# pqm_v2_page4.net
KiCad netlist of a schematic drawn in Altium Designer
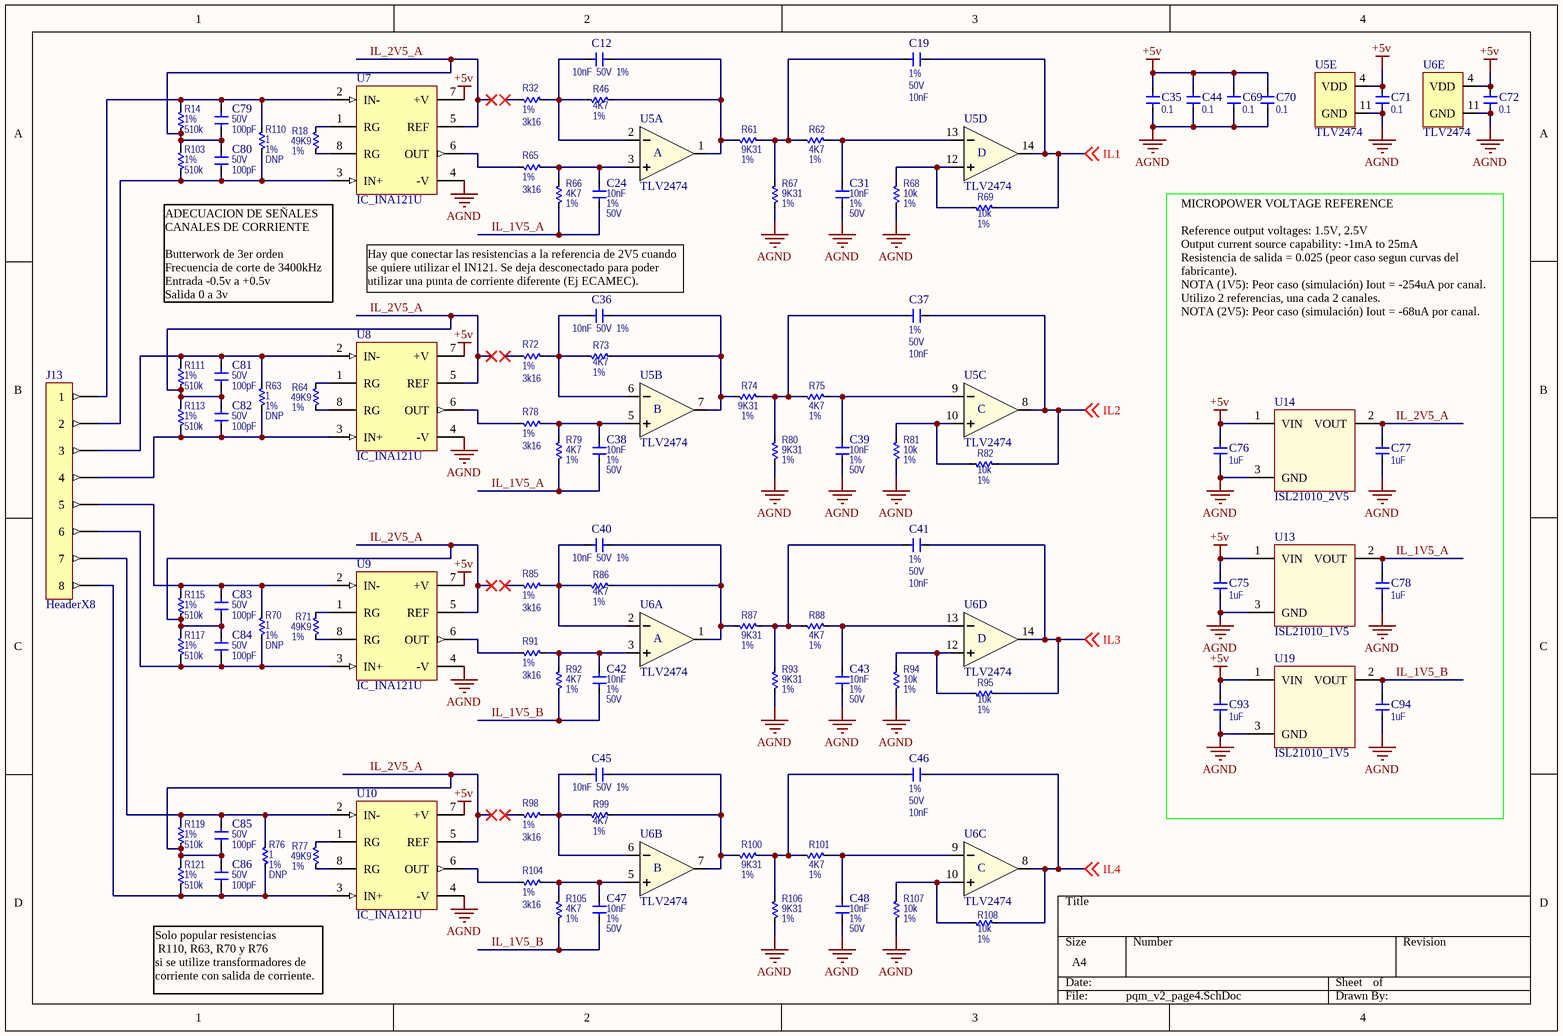
[diagram p0: pqm_v2_page4.SchDoc]

(export (version "E")
  (design (tool "Eeschema 10.0.6"))
  (components
    (comp (ref "C12")
      (value "10nF")
      (footprint "CAPC2013X110N")
      (description "CAP CER 10000PF 50V NP0 0805")
      (fields
        (field (name "MANUFACTURER") "Murata Electronics North America")
        (field (name "TOLERANCE") "1%")
        (field (name "VOLTAGE RATING") "50V")
        (field (name "DIGIKEY PART NUMBER") "490-8295-1-ND")
      )
      (libsource (lib "pqm_v2_lib_cap") (part "CAP_GRM2195C1H103FA01D_MURATA"))
    )
    (comp (ref "C19")
      (value "10nF")
      (footprint "CAPC2013X110N")
      (description "CAP CER 10000PF 50V NP0 0805")
      (fields
        (field (name "MANUFACTURER") "Murata Electronics North America")
        (field (name "TOLERANCE") "1%")
        (field (name "VOLTAGE RATING") "50V")
        (field (name "DIGIKEY PART NUMBER") "490-8295-1-ND")
      )
      (libsource (lib "pqm_v2_lib_cap") (part "CAP_GRM2195C1H103FA01D_MURATA"))
    )
    (comp (ref "C24")
      (value "10nF")
      (footprint "CAPC2013X110N")
      (description "CAP CER 10000PF 50V NP0 0805")
      (fields
        (field (name "MANUFACTURER") "Murata Electronics North America")
        (field (name "TOLERANCE") "1%")
        (field (name "VOLTAGE RATING") "50V")
        (field (name "DIGIKEY PART NUMBER") "490-8295-1-ND")
      )
      (libsource (lib "pqm_v2_lib_cap") (part "CAP_GRM2195C1H103FA01D_MURATA"))
    )
    (comp (ref "C31")
      (value "10nF")
      (footprint "CAPC2013X110N")
      (description "CAP CER 10000PF 50V NP0 0805")
      (fields
        (field (name "MANUFACTURER") "Murata Electronics North America")
        (field (name "TOLERANCE") "1%")
        (field (name "VOLTAGE RATING") "50V")
        (field (name "DIGIKEY PART NUMBER") "490-8295-1-ND")
      )
      (libsource (lib "pqm_v2_lib_cap") (part "CAP_GRM2195C1H103FA01D_MURATA"))
    )
    (comp (ref "C35")
      (value "0.1")
      (footprint "CAPC2013X110N")
      (description "CAP CER 0.1UF 25V 10% X7R 0805")
      (fields (field (name "MANUFACTURER") "Yageo") (field (name "TOLERANCE") "10%"))
      (libsource (lib "pqm_v2_lib_cap") (part "CAP_CC0805KRX7R8BB104_YAGEO"))
    )
    (comp (ref "C36")
      (value "10nF")
      (footprint "CAPC2013X110N")
      (description "CAP CER 10000PF 50V NP0 0805")
      (fields
        (field (name "MANUFACTURER") "Murata Electronics North America")
        (field (name "TOLERANCE") "1%")
        (field (name "VOLTAGE RATING") "50V")
        (field (name "DIGIKEY PART NUMBER") "490-8295-1-ND")
      )
      (libsource (lib "pqm_v2_lib_cap") (part "CAP_GRM2195C1H103FA01D_MURATA"))
    )
    (comp (ref "C37")
      (value "10nF")
      (footprint "CAPC2013X110N")
      (description "CAP CER 10000PF 50V NP0 0805")
      (fields
        (field (name "MANUFACTURER") "Murata Electronics North America")
        (field (name "TOLERANCE") "1%")
        (field (name "VOLTAGE RATING") "50V")
        (field (name "DIGIKEY PART NUMBER") "490-8295-1-ND")
      )
      (libsource (lib "pqm_v2_lib_cap") (part "CAP_GRM2195C1H103FA01D_MURATA"))
    )
    (comp (ref "C38")
      (value "10nF")
      (footprint "CAPC2013X110N")
      (description "CAP CER 10000PF 50V NP0 0805")
      (fields
        (field (name "MANUFACTURER") "Murata Electronics North America")
        (field (name "TOLERANCE") "1%")
        (field (name "VOLTAGE RATING") "50V")
        (field (name "DIGIKEY PART NUMBER") "490-8295-1-ND")
      )
      (libsource (lib "pqm_v2_lib_cap") (part "CAP_GRM2195C1H103FA01D_MURATA"))
    )
    (comp (ref "C39")
      (value "10nF")
      (footprint "CAPC2013X110N")
      (description "CAP CER 10000PF 50V NP0 0805")
      (fields
        (field (name "MANUFACTURER") "Murata Electronics North America")
        (field (name "TOLERANCE") "1%")
        (field (name "VOLTAGE RATING") "50V")
        (field (name "DIGIKEY PART NUMBER") "490-8295-1-ND")
      )
      (libsource (lib "pqm_v2_lib_cap") (part "CAP_GRM2195C1H103FA01D_MURATA"))
    )
    (comp (ref "C40")
      (value "10nF")
      (footprint "CAPC2013X110N")
      (description "CAP CER 10000PF 50V NP0 0805")
      (fields
        (field (name "MANUFACTURER") "Murata Electronics North America")
        (field (name "TOLERANCE") "1%")
        (field (name "VOLTAGE RATING") "50V")
        (field (name "DIGIKEY PART NUMBER") "490-8295-1-ND")
      )
      (libsource (lib "pqm_v2_lib_cap") (part "CAP_GRM2195C1H103FA01D_MURATA"))
    )
    (comp (ref "C41")
      (value "10nF")
      (footprint "CAPC2013X110N")
      (description "CAP CER 10000PF 50V NP0 0805")
      (fields
        (field (name "MANUFACTURER") "Murata Electronics North America")
        (field (name "TOLERANCE") "1%")
        (field (name "VOLTAGE RATING") "50V")
        (field (name "DIGIKEY PART NUMBER") "490-8295-1-ND")
      )
      (libsource (lib "pqm_v2_lib_cap") (part "CAP_GRM2195C1H103FA01D_MURATA"))
    )
    (comp (ref "C42")
      (value "10nF")
      (footprint "CAPC2013X110N")
      (description "CAP CER 10000PF 50V NP0 0805")
      (fields
        (field (name "MANUFACTURER") "Murata Electronics North America")
        (field (name "TOLERANCE") "1%")
        (field (name "VOLTAGE RATING") "50V")
        (field (name "DIGIKEY PART NUMBER") "490-8295-1-ND")
      )
      (libsource (lib "pqm_v2_lib_cap") (part "CAP_GRM2195C1H103FA01D_MURATA"))
    )
    (comp (ref "C43")
      (value "10nF")
      (footprint "CAPC2013X110N")
      (description "CAP CER 10000PF 50V NP0 0805")
      (fields
        (field (name "MANUFACTURER") "Murata Electronics North America")
        (field (name "TOLERANCE") "1%")
        (field (name "VOLTAGE RATING") "50V")
        (field (name "DIGIKEY PART NUMBER") "490-8295-1-ND")
      )
      (libsource (lib "pqm_v2_lib_cap") (part "CAP_GRM2195C1H103FA01D_MURATA"))
    )
    (comp (ref "C44")
      (value "0.1")
      (footprint "CAPC2013X110N")
      (description "CAP CER 0.1UF 25V 10% X7R 0805")
      (fields (field (name "MANUFACTURER") "Yageo") (field (name "TOLERANCE") "10%"))
      (libsource (lib "pqm_v2_lib_cap") (part "CAP_CC0805KRX7R8BB104_YAGEO"))
    )
    (comp (ref "C45")
      (value "10nF")
      (footprint "CAPC2013X110N")
      (description "CAP CER 10000PF 50V NP0 0805")
      (fields
        (field (name "MANUFACTURER") "Murata Electronics North America")
        (field (name "TOLERANCE") "1%")
        (field (name "VOLTAGE RATING") "50V")
        (field (name "DIGIKEY PART NUMBER") "490-8295-1-ND")
      )
      (libsource (lib "pqm_v2_lib_cap") (part "CAP_GRM2195C1H103FA01D_MURATA"))
    )
    (comp (ref "C46")
      (value "10nF")
      (footprint "CAPC2013X110N")
      (description "CAP CER 10000PF 50V NP0 0805")
      (fields
        (field (name "MANUFACTURER") "Murata Electronics North America")
        (field (name "TOLERANCE") "1%")
        (field (name "VOLTAGE RATING") "50V")
        (field (name "DIGIKEY PART NUMBER") "490-8295-1-ND")
      )
      (libsource (lib "pqm_v2_lib_cap") (part "CAP_GRM2195C1H103FA01D_MURATA"))
    )
    (comp (ref "C47")
      (value "10nF")
      (footprint "CAPC2013X110N")
      (description "CAP CER 10000PF 50V NP0 0805")
      (fields
        (field (name "MANUFACTURER") "Murata Electronics North America")
        (field (name "TOLERANCE") "1%")
        (field (name "VOLTAGE RATING") "50V")
        (field (name "DIGIKEY PART NUMBER") "490-8295-1-ND")
      )
      (libsource (lib "pqm_v2_lib_cap") (part "CAP_GRM2195C1H103FA01D_MURATA"))
    )
    (comp (ref "C48")
      (value "10nF")
      (footprint "CAPC2013X110N")
      (description "CAP CER 10000PF 50V NP0 0805")
      (fields
        (field (name "MANUFACTURER") "Murata Electronics North America")
        (field (name "TOLERANCE") "1%")
        (field (name "VOLTAGE RATING") "50V")
        (field (name "DIGIKEY PART NUMBER") "490-8295-1-ND")
      )
      (libsource (lib "pqm_v2_lib_cap") (part "CAP_GRM2195C1H103FA01D_MURATA"))
    )
    (comp (ref "C69")
      (value "0.1")
      (footprint "CAPC2013X110N")
      (description "CAP CER 0.1UF 25V 10% X7R 0805")
      (fields (field (name "MANUFACTURER") "Yageo") (field (name "TOLERANCE") "10%"))
      (libsource (lib "pqm_v2_lib_cap") (part "CAP_CC0805KRX7R8BB104_YAGEO"))
    )
    (comp (ref "C70")
      (value "0.1")
      (footprint "CAPC2013X110N")
      (description "CAP CER 0.1UF 25V 10% X7R 0805")
      (fields (field (name "MANUFACTURER") "Yageo") (field (name "TOLERANCE") "10%"))
      (libsource (lib "pqm_v2_lib_cap") (part "CAP_CC0805KRX7R8BB104_YAGEO"))
    )
    (comp (ref "C71")
      (value "0.1")
      (footprint "CAPC2013X110N")
      (description "CAP CER 0.1UF 25V 10% X7R 0805")
      (fields (field (name "MANUFACTURER") "Yageo") (field (name "TOLERANCE") "10%"))
      (libsource (lib "pqm_v2_lib_cap") (part "CAP_CC0805KRX7R8BB104_YAGEO"))
    )
    (comp (ref "C72")
      (value "0.1")
      (footprint "CAPC2013X110N")
      (description "CAP CER 0.1UF 25V 10% X7R 0805")
      (fields (field (name "MANUFACTURER") "Yageo") (field (name "TOLERANCE") "10%"))
      (libsource (lib "pqm_v2_lib_cap") (part "CAP_CC0805KRX7R8BB104_YAGEO"))
    )
    (comp (ref "C75")
      (value "1uF")
      (footprint "CAPC2013X110N")
      (description "CAP CER 1UF 16V X7R 0805")
      (fields (field (name "MANUFACTURER") "YAGEO") (field (name "TOLERANCE") "10%"))
      (libsource (lib "pqm_v2_lib_cap") (part "CAP_CC0805KKX7R7BB105_YAGEO"))
    )
    (comp (ref "C76")
      (value "1uF")
      (footprint "CAPC2013X110N")
      (description "CAP CER 1UF 16V X7R 0805")
      (fields (field (name "MANUFACTURER") "YAGEO") (field (name "TOLERANCE") "10%"))
      (libsource (lib "pqm_v2_lib_cap") (part "CAP_CC0805KKX7R7BB105_YAGEO"))
    )
    (comp (ref "C77")
      (value "1uF")
      (footprint "CAPC2013X110N")
      (description "CAP CER 1UF 16V X7R 0805")
      (fields (field (name "MANUFACTURER") "YAGEO") (field (name "TOLERANCE") "10%"))
      (libsource (lib "pqm_v2_lib_cap") (part "CAP_CC0805KKX7R7BB105_YAGEO"))
    )
    (comp (ref "C78")
      (value "1uF")
      (footprint "CAPC2013X110N")
      (description "CAP CER 1UF 16V X7R 0805")
      (fields (field (name "MANUFACTURER") "YAGEO") (field (name "TOLERANCE") "10%"))
      (libsource (lib "pqm_v2_lib_cap") (part "CAP_CC0805KKX7R7BB105_YAGEO"))
    )
    (comp (ref "C79")
      (value "100pF")
      (footprint "CAPC2013X110N")
      (description "CAP CER 100PF 50V NPO 0805")
      (fields
        (field (name "MANUFACTURER") "Yageo")
        (field (name "TOLERANCE") "5%")
        (field (name "VOLTAGE RATING") "50V")
      )
      (libsource (lib "pqm_v2_lib_cap") (part "CAP_CC0805JRNPO9BN101_YAGEO"))
    )
    (comp (ref "C80")
      (value "100pF")
      (footprint "CAPC2013X110N")
      (description "CAP CER 100PF 50V NPO 0805")
      (fields
        (field (name "MANUFACTURER") "Yageo")
        (field (name "TOLERANCE") "5%")
        (field (name "VOLTAGE RATING") "50V")
      )
      (libsource (lib "pqm_v2_lib_cap") (part "CAP_CC0805JRNPO9BN101_YAGEO"))
    )
    (comp (ref "C81")
      (value "100pF")
      (footprint "CAPC2013X110N")
      (description "CAP CER 100PF 50V NPO 0805")
      (fields
        (field (name "MANUFACTURER") "Yageo")
        (field (name "TOLERANCE") "5%")
        (field (name "VOLTAGE RATING") "50V")
      )
      (libsource (lib "pqm_v2_lib_cap") (part "CAP_CC0805JRNPO9BN101_YAGEO"))
    )
    (comp (ref "C82")
      (value "100pF")
      (footprint "CAPC2013X110N")
      (description "CAP CER 100PF 50V NPO 0805")
      (fields
        (field (name "MANUFACTURER") "Yageo")
        (field (name "TOLERANCE") "5%")
        (field (name "VOLTAGE RATING") "50V")
      )
      (libsource (lib "pqm_v2_lib_cap") (part "CAP_CC0805JRNPO9BN101_YAGEO"))
    )
    (comp (ref "C83")
      (value "100pF")
      (footprint "CAPC2013X110N")
      (description "CAP CER 100PF 50V NPO 0805")
      (fields
        (field (name "MANUFACTURER") "Yageo")
        (field (name "TOLERANCE") "5%")
        (field (name "VOLTAGE RATING") "50V")
      )
      (libsource (lib "pqm_v2_lib_cap") (part "CAP_CC0805JRNPO9BN101_YAGEO"))
    )
    (comp (ref "C84")
      (value "100pF")
      (footprint "CAPC2013X110N")
      (description "CAP CER 100PF 50V NPO 0805")
      (fields
        (field (name "MANUFACTURER") "Yageo")
        (field (name "TOLERANCE") "5%")
        (field (name "VOLTAGE RATING") "50V")
      )
      (libsource (lib "pqm_v2_lib_cap") (part "CAP_CC0805JRNPO9BN101_YAGEO"))
    )
    (comp (ref "C85")
      (value "100pF")
      (footprint "CAPC2013X110N")
      (description "CAP CER 100PF 50V NPO 0805")
      (fields
        (field (name "MANUFACTURER") "Yageo")
        (field (name "TOLERANCE") "5%")
        (field (name "VOLTAGE RATING") "50V")
      )
      (libsource (lib "pqm_v2_lib_cap") (part "CAP_CC0805JRNPO9BN101_YAGEO"))
    )
    (comp (ref "C86")
      (value "100pF")
      (footprint "CAPC2013X110N")
      (description "CAP CER 100PF 50V NPO 0805")
      (fields
        (field (name "MANUFACTURER") "Yageo")
        (field (name "TOLERANCE") "5%")
        (field (name "VOLTAGE RATING") "50V")
      )
      (libsource (lib "pqm_v2_lib_cap") (part "CAP_CC0805JRNPO9BN101_YAGEO"))
    )
    (comp (ref "C93")
      (value "1uF")
      (footprint "CAPC2013X110N")
      (description "CAP CER 1UF 16V X7R 0805")
      (fields (field (name "MANUFACTURER") "YAGEO") (field (name "TOLERANCE") "10%"))
      (libsource (lib "pqm_v2_lib_cap") (part "CAP_CC0805KKX7R7BB105_YAGEO"))
    )
    (comp (ref "C94")
      (value "1uF")
      (footprint "CAPC2013X110N")
      (description "CAP CER 1UF 16V X7R 0805")
      (fields (field (name "MANUFACTURER") "YAGEO") (field (name "TOLERANCE") "10%"))
      (libsource (lib "pqm_v2_lib_cap") (part "CAP_CC0805KKX7R7BB105_YAGEO"))
    )
    (comp (ref "J13")
      (value "HeaderX8")
      (footprint "BorneraX8")
      (libsource (lib "pqm_v2_lib_connectors") (part "CON_HeaderX8"))
    )
    (comp (ref "R14")
      (value "510k")
      (footprint "RESC2013X065BN")
      (description "RES SMD 510K OHM 1% 1/8W 0805")
      (fields
        (field (name "MANUFACTURER") "Yageo")
        (field (name "DIGIKEY PART NUMBER") "311-510KCRCT-ND")
        (field (name "TOLERANCE") "1%")
      )
      (libsource (lib "pqm_v2_lib_res") (part "RES_RC0805FR-07510KL_YAGEO"))
    )
    (comp (ref "R18")
      (value "49K9")
      (footprint "RESC2013X065BN")
      (description "RES SMD 49.9K OHM 1% 1/8W 0805")
      (fields
        (field (name "MANUFACTURER") "Yageo")
        (field (name "DIGIKEY PART NUMBER") "311-49.9KCRCT-ND")
        (field (name "TOLERANCE") "1%")
      )
      (libsource (lib "pqm_v2_lib_res") (part "RES_RC0805FR-0749K9L_YAGEO"))
    )
    (comp (ref "R32")
      (value "3k16")
      (footprint "RESC2013X065BN")
      (description "RES SMD 3.16K OHM 1% 1/8W 0805")
      (fields
        (field (name "TOLERANCE") "1%")
        (field (name "MANUFACTURER") "Yageo")
        (field (name "DIGIKEY PART NUMBER") "311-3.16KCRCT-ND")
      )
      (libsource (lib "pqm_v2_lib_res") (part "RES_RC0805FR-073K16L_YAGEO"))
    )
    (comp (ref "R46")
      (value "4K7")
      (footprint "RESC2013X065BN")
      (description "RES SMD 4.7K OHM 1% 1/8W 0805")
      (fields
        (field (name "TOLERANCE") "1%")
        (field (name "MANUFACTURER") "Yageo")
        (field (name "DIGIKEY PART NUMBER") "311-4.70KCRCT-ND")
      )
      (libsource (lib "pqm_v2_lib_res") (part "RES_RC0805FR-074K7L_YAGEO"))
    )
    (comp (ref "R61")
      (value "9K31")
      (footprint "RESC2013X065BN")
      (description "RES SMD 9.31K OHM 1% 1/8W 0805")
      (fields
        (field (name "TOLERANCE") "1%")
        (field (name "MANUFACTURER") "Yageo")
        (field (name "DIGIKEY PART NUMBER") "311-9.31KCRCT-ND")
      )
      (libsource (lib "pqm_v2_lib_res") (part "RES_RC0805FR-079K31L_YAGEO"))
    )
    (comp (ref "R62")
      (value "4K7")
      (footprint "RESC2013X065BN")
      (description "RES SMD 4.7K OHM 1% 1/8W 0805")
      (fields
        (field (name "TOLERANCE") "1%")
        (field (name "MANUFACTURER") "Yageo")
        (field (name "DIGIKEY PART NUMBER") "311-4.70KCRCT-ND")
      )
      (libsource (lib "pqm_v2_lib_res") (part "RES_RC0805FR-074K7L_YAGEO"))
    )
    (comp (ref "R63")
      (value "1")
      (footprint "RESC2013X065BN")
      (description "RES SMD 1 OHM 1% 1/8W 0805")
      (fields
        (field (name "MANUFACTURER") "Yageo")
        (field (name "DIGIKEY PART NUMBER") "311-1.00CRCT-ND")
        (field (name "TOLERANCE") "1%")
      )
      (libsource (lib "pqm_v2_lib_res") (part "RES_RC0805FR-071RL_YAGEO"))
    )
    (comp (ref "R64")
      (value "49K9")
      (footprint "RESC2013X065BN")
      (description "RES SMD 49.9K OHM 1% 1/8W 0805")
      (fields
        (field (name "MANUFACTURER") "Yageo")
        (field (name "DIGIKEY PART NUMBER") "311-49.9KCRCT-ND")
        (field (name "TOLERANCE") "1%")
      )
      (libsource (lib "pqm_v2_lib_res") (part "RES_RC0805FR-0749K9L_YAGEO"))
    )
    (comp (ref "R65")
      (value "3k16")
      (footprint "RESC2013X065BN")
      (description "RES SMD 3.16K OHM 1% 1/8W 0805")
      (fields
        (field (name "TOLERANCE") "1%")
        (field (name "MANUFACTURER") "Yageo")
        (field (name "DIGIKEY PART NUMBER") "311-3.16KCRCT-ND")
      )
      (libsource (lib "pqm_v2_lib_res") (part "RES_RC0805FR-073K16L_YAGEO"))
    )
    (comp (ref "R66")
      (value "4K7")
      (footprint "RESC2013X065BN")
      (description "RES SMD 4.7K OHM 1% 1/8W 0805")
      (fields
        (field (name "TOLERANCE") "1%")
        (field (name "MANUFACTURER") "Yageo")
        (field (name "DIGIKEY PART NUMBER") "311-4.70KCRCT-ND")
      )
      (libsource (lib "pqm_v2_lib_res") (part "RES_RC0805FR-074K7L_YAGEO"))
    )
    (comp (ref "R67")
      (value "9K31")
      (footprint "RESC2013X065BN")
      (description "RES SMD 9.31K OHM 1% 1/8W 0805")
      (fields
        (field (name "TOLERANCE") "1%")
        (field (name "MANUFACTURER") "Yageo")
        (field (name "DIGIKEY PART NUMBER") "311-9.31KCRCT-ND")
      )
      (libsource (lib "pqm_v2_lib_res") (part "RES_RC0805FR-079K31L_YAGEO"))
    )
    (comp (ref "R68")
      (value "10k")
      (footprint "RESC2013X065BN")
      (description "RES SMD 10K OHM 1% 1/8W 0805")
      (fields
        (field (name "TOLERANCE") "1%")
        (field (name "MANUFACTURER") "Yageo")
        (field (name "DIGIKEY PART NUMBER") "311-10.0KCRCT-ND")
      )
      (libsource (lib "pqm_v2_lib_res") (part "RES_RC0805FR-0710KL_YAGEO"))
    )
    (comp (ref "R69")
      (value "10k")
      (footprint "RESC2013X065BN")
      (description "RES SMD 10K OHM 1% 1/8W 0805")
      (fields
        (field (name "TOLERANCE") "1%")
        (field (name "MANUFACTURER") "Yageo")
        (field (name "DIGIKEY PART NUMBER") "311-10.0KCRCT-ND")
      )
      (libsource (lib "pqm_v2_lib_res") (part "RES_RC0805FR-0710KL_YAGEO"))
    )
    (comp (ref "R70")
      (value "1")
      (footprint "RESC2013X065BN")
      (description "RES SMD 1 OHM 1% 1/8W 0805")
      (fields
        (field (name "MANUFACTURER") "Yageo")
        (field (name "DIGIKEY PART NUMBER") "311-1.00CRCT-ND")
        (field (name "TOLERANCE") "1%")
      )
      (libsource (lib "pqm_v2_lib_res") (part "RES_RC0805FR-071RL_YAGEO"))
    )
    (comp (ref "R71")
      (value "49K9")
      (footprint "RESC2013X065BN")
      (description "RES SMD 49.9K OHM 1% 1/8W 0805")
      (fields
        (field (name "MANUFACTURER") "Yageo")
        (field (name "DIGIKEY PART NUMBER") "311-49.9KCRCT-ND")
        (field (name "TOLERANCE") "1%")
      )
      (libsource (lib "pqm_v2_lib_res") (part "RES_RC0805FR-0749K9L_YAGEO"))
    )
    (comp (ref "R72")
      (value "3k16")
      (footprint "RESC2013X065BN")
      (description "RES SMD 3.16K OHM 1% 1/8W 0805")
      (fields
        (field (name "TOLERANCE") "1%")
        (field (name "MANUFACTURER") "Yageo")
        (field (name "DIGIKEY PART NUMBER") "311-3.16KCRCT-ND")
      )
      (libsource (lib "pqm_v2_lib_res") (part "RES_RC0805FR-073K16L_YAGEO"))
    )
    (comp (ref "R73")
      (value "4K7")
      (footprint "RESC2013X065BN")
      (description "RES SMD 4.7K OHM 1% 1/8W 0805")
      (fields
        (field (name "TOLERANCE") "1%")
        (field (name "MANUFACTURER") "Yageo")
        (field (name "DIGIKEY PART NUMBER") "311-4.70KCRCT-ND")
      )
      (libsource (lib "pqm_v2_lib_res") (part "RES_RC0805FR-074K7L_YAGEO"))
    )
    (comp (ref "R74")
      (value "9K31")
      (footprint "RESC2013X065BN")
      (description "RES SMD 9.31K OHM 1% 1/8W 0805")
      (fields
        (field (name "TOLERANCE") "1%")
        (field (name "MANUFACTURER") "Yageo")
        (field (name "DIGIKEY PART NUMBER") "311-9.31KCRCT-ND")
      )
      (libsource (lib "pqm_v2_lib_res") (part "RES_RC0805FR-079K31L_YAGEO"))
    )
    (comp (ref "R75")
      (value "4K7")
      (footprint "RESC2013X065BN")
      (description "RES SMD 4.7K OHM 1% 1/8W 0805")
      (fields
        (field (name "TOLERANCE") "1%")
        (field (name "MANUFACTURER") "Yageo")
        (field (name "DIGIKEY PART NUMBER") "311-4.70KCRCT-ND")
      )
      (libsource (lib "pqm_v2_lib_res") (part "RES_RC0805FR-074K7L_YAGEO"))
    )
    (comp (ref "R76")
      (value "1")
      (footprint "RESC2013X065BN")
      (description "RES SMD 1 OHM 1% 1/8W 0805")
      (fields
        (field (name "MANUFACTURER") "Yageo")
        (field (name "DIGIKEY PART NUMBER") "311-1.00CRCT-ND")
        (field (name "TOLERANCE") "1%")
      )
      (libsource (lib "pqm_v2_lib_res") (part "RES_RC0805FR-071RL_YAGEO"))
    )
    (comp (ref "R77")
      (value "49K9")
      (footprint "RESC2013X065BN")
      (description "RES SMD 49.9K OHM 1% 1/8W 0805")
      (fields
        (field (name "MANUFACTURER") "Yageo")
        (field (name "DIGIKEY PART NUMBER") "311-49.9KCRCT-ND")
        (field (name "TOLERANCE") "1%")
      )
      (libsource (lib "pqm_v2_lib_res") (part "RES_RC0805FR-0749K9L_YAGEO"))
    )
    (comp (ref "R78")
      (value "3k16")
      (footprint "RESC2013X065BN")
      (description "RES SMD 3.16K OHM 1% 1/8W 0805")
      (fields
        (field (name "TOLERANCE") "1%")
        (field (name "MANUFACTURER") "Yageo")
        (field (name "DIGIKEY PART NUMBER") "311-3.16KCRCT-ND")
      )
      (libsource (lib "pqm_v2_lib_res") (part "RES_RC0805FR-073K16L_YAGEO"))
    )
    (comp (ref "R79")
      (value "4K7")
      (footprint "RESC2013X065BN")
      (description "RES SMD 4.7K OHM 1% 1/8W 0805")
      (fields
        (field (name "TOLERANCE") "1%")
        (field (name "MANUFACTURER") "Yageo")
        (field (name "DIGIKEY PART NUMBER") "311-4.70KCRCT-ND")
      )
      (libsource (lib "pqm_v2_lib_res") (part "RES_RC0805FR-074K7L_YAGEO"))
    )
    (comp (ref "R80")
      (value "9K31")
      (footprint "RESC2013X065BN")
      (description "RES SMD 9.31K OHM 1% 1/8W 0805")
      (fields
        (field (name "TOLERANCE") "1%")
        (field (name "MANUFACTURER") "Yageo")
        (field (name "DIGIKEY PART NUMBER") "311-9.31KCRCT-ND")
      )
      (libsource (lib "pqm_v2_lib_res") (part "RES_RC0805FR-079K31L_YAGEO"))
    )
    (comp (ref "R81")
      (value "10k")
      (footprint "RESC2013X065BN")
      (description "RES SMD 10K OHM 1% 1/8W 0805")
      (fields
        (field (name "TOLERANCE") "1%")
        (field (name "MANUFACTURER") "Yageo")
        (field (name "DIGIKEY PART NUMBER") "311-10.0KCRCT-ND")
      )
      (libsource (lib "pqm_v2_lib_res") (part "RES_RC0805FR-0710KL_YAGEO"))
    )
    (comp (ref "R82")
      (value "10k")
      (footprint "RESC2013X065BN")
      (description "RES SMD 10K OHM 1% 1/8W 0805")
      (fields
        (field (name "TOLERANCE") "1%")
        (field (name "MANUFACTURER") "Yageo")
        (field (name "DIGIKEY PART NUMBER") "311-10.0KCRCT-ND")
      )
      (libsource (lib "pqm_v2_lib_res") (part "RES_RC0805FR-0710KL_YAGEO"))
    )
    (comp (ref "R85")
      (value "3k16")
      (footprint "RESC2013X065BN")
      (description "RES SMD 3.16K OHM 1% 1/8W 0805")
      (fields
        (field (name "TOLERANCE") "1%")
        (field (name "MANUFACTURER") "Yageo")
        (field (name "DIGIKEY PART NUMBER") "311-3.16KCRCT-ND")
      )
      (libsource (lib "pqm_v2_lib_res") (part "RES_RC0805FR-073K16L_YAGEO"))
    )
    (comp (ref "R86")
      (value "4K7")
      (footprint "RESC2013X065BN")
      (description "RES SMD 4.7K OHM 1% 1/8W 0805")
      (fields
        (field (name "TOLERANCE") "1%")
        (field (name "MANUFACTURER") "Yageo")
        (field (name "DIGIKEY PART NUMBER") "311-4.70KCRCT-ND")
      )
      (libsource (lib "pqm_v2_lib_res") (part "RES_RC0805FR-074K7L_YAGEO"))
    )
    (comp (ref "R87")
      (value "9K31")
      (footprint "RESC2013X065BN")
      (description "RES SMD 9.31K OHM 1% 1/8W 0805")
      (fields
        (field (name "TOLERANCE") "1%")
        (field (name "MANUFACTURER") "Yageo")
        (field (name "DIGIKEY PART NUMBER") "311-9.31KCRCT-ND")
      )
      (libsource (lib "pqm_v2_lib_res") (part "RES_RC0805FR-079K31L_YAGEO"))
    )
    (comp (ref "R88")
      (value "4K7")
      (footprint "RESC2013X065BN")
      (description "RES SMD 4.7K OHM 1% 1/8W 0805")
      (fields
        (field (name "TOLERANCE") "1%")
        (field (name "MANUFACTURER") "Yageo")
        (field (name "DIGIKEY PART NUMBER") "311-4.70KCRCT-ND")
      )
      (libsource (lib "pqm_v2_lib_res") (part "RES_RC0805FR-074K7L_YAGEO"))
    )
    (comp (ref "R91")
      (value "3k16")
      (footprint "RESC2013X065BN")
      (description "RES SMD 3.16K OHM 1% 1/8W 0805")
      (fields
        (field (name "TOLERANCE") "1%")
        (field (name "MANUFACTURER") "Yageo")
        (field (name "DIGIKEY PART NUMBER") "311-3.16KCRCT-ND")
      )
      (libsource (lib "pqm_v2_lib_res") (part "RES_RC0805FR-073K16L_YAGEO"))
    )
    (comp (ref "R92")
      (value "4K7")
      (footprint "RESC2013X065BN")
      (description "RES SMD 4.7K OHM 1% 1/8W 0805")
      (fields
        (field (name "TOLERANCE") "1%")
        (field (name "MANUFACTURER") "Yageo")
        (field (name "DIGIKEY PART NUMBER") "311-4.70KCRCT-ND")
      )
      (libsource (lib "pqm_v2_lib_res") (part "RES_RC0805FR-074K7L_YAGEO"))
    )
    (comp (ref "R93")
      (value "9K31")
      (footprint "RESC2013X065BN")
      (description "RES SMD 9.31K OHM 1% 1/8W 0805")
      (fields
        (field (name "TOLERANCE") "1%")
        (field (name "MANUFACTURER") "Yageo")
        (field (name "DIGIKEY PART NUMBER") "311-9.31KCRCT-ND")
      )
      (libsource (lib "pqm_v2_lib_res") (part "RES_RC0805FR-079K31L_YAGEO"))
    )
    (comp (ref "R94")
      (value "10k")
      (footprint "RESC2013X065BN")
      (description "RES SMD 10K OHM 1% 1/8W 0805")
      (fields
        (field (name "TOLERANCE") "1%")
        (field (name "MANUFACTURER") "Yageo")
        (field (name "DIGIKEY PART NUMBER") "311-10.0KCRCT-ND")
      )
      (libsource (lib "pqm_v2_lib_res") (part "RES_RC0805FR-0710KL_YAGEO"))
    )
    (comp (ref "R95")
      (value "10k")
      (footprint "RESC2013X065BN")
      (description "RES SMD 10K OHM 1% 1/8W 0805")
      (fields
        (field (name "TOLERANCE") "1%")
        (field (name "MANUFACTURER") "Yageo")
        (field (name "DIGIKEY PART NUMBER") "311-10.0KCRCT-ND")
      )
      (libsource (lib "pqm_v2_lib_res") (part "RES_RC0805FR-0710KL_YAGEO"))
    )
    (comp (ref "R98")
      (value "3k16")
      (footprint "RESC2013X065BN")
      (description "RES SMD 3.16K OHM 1% 1/8W 0805")
      (fields
        (field (name "TOLERANCE") "1%")
        (field (name "MANUFACTURER") "Yageo")
        (field (name "DIGIKEY PART NUMBER") "311-3.16KCRCT-ND")
      )
      (libsource (lib "pqm_v2_lib_res") (part "RES_RC0805FR-073K16L_YAGEO"))
    )
    (comp (ref "R99")
      (value "4K7")
      (footprint "RESC2013X065BN")
      (description "RES SMD 4.7K OHM 1% 1/8W 0805")
      (fields
        (field (name "TOLERANCE") "1%")
        (field (name "MANUFACTURER") "Yageo")
        (field (name "DIGIKEY PART NUMBER") "311-4.70KCRCT-ND")
      )
      (libsource (lib "pqm_v2_lib_res") (part "RES_RC0805FR-074K7L_YAGEO"))
    )
    (comp (ref "R100")
      (value "9K31")
      (footprint "RESC2013X065BN")
      (description "RES SMD 9.31K OHM 1% 1/8W 0805")
      (fields
        (field (name "TOLERANCE") "1%")
        (field (name "MANUFACTURER") "Yageo")
        (field (name "DIGIKEY PART NUMBER") "311-9.31KCRCT-ND")
      )
      (libsource (lib "pqm_v2_lib_res") (part "RES_RC0805FR-079K31L_YAGEO"))
    )
    (comp (ref "R101")
      (value "4K7")
      (footprint "RESC2013X065BN")
      (description "RES SMD 4.7K OHM 1% 1/8W 0805")
      (fields
        (field (name "TOLERANCE") "1%")
        (field (name "MANUFACTURER") "Yageo")
        (field (name "DIGIKEY PART NUMBER") "311-4.70KCRCT-ND")
      )
      (libsource (lib "pqm_v2_lib_res") (part "RES_RC0805FR-074K7L_YAGEO"))
    )
    (comp (ref "R103")
      (value "510k")
      (footprint "RESC2013X065BN")
      (description "RES SMD 510K OHM 1% 1/8W 0805")
      (fields
        (field (name "MANUFACTURER") "Yageo")
        (field (name "DIGIKEY PART NUMBER") "311-510KCRCT-ND")
        (field (name "TOLERANCE") "1%")
      )
      (libsource (lib "pqm_v2_lib_res") (part "RES_RC0805FR-07510KL_YAGEO"))
    )
    (comp (ref "R104")
      (value "3k16")
      (footprint "RESC2013X065BN")
      (description "RES SMD 3.16K OHM 1% 1/8W 0805")
      (fields
        (field (name "TOLERANCE") "1%")
        (field (name "MANUFACTURER") "Yageo")
        (field (name "DIGIKEY PART NUMBER") "311-3.16KCRCT-ND")
      )
      (libsource (lib "pqm_v2_lib_res") (part "RES_RC0805FR-073K16L_YAGEO"))
    )
    (comp (ref "R105")
      (value "4K7")
      (footprint "RESC2013X065BN")
      (description "RES SMD 4.7K OHM 1% 1/8W 0805")
      (fields
        (field (name "TOLERANCE") "1%")
        (field (name "MANUFACTURER") "Yageo")
        (field (name "DIGIKEY PART NUMBER") "311-4.70KCRCT-ND")
      )
      (libsource (lib "pqm_v2_lib_res") (part "RES_RC0805FR-074K7L_YAGEO"))
    )
    (comp (ref "R106")
      (value "9K31")
      (footprint "RESC2013X065BN")
      (description "RES SMD 9.31K OHM 1% 1/8W 0805")
      (fields
        (field (name "TOLERANCE") "1%")
        (field (name "MANUFACTURER") "Yageo")
        (field (name "DIGIKEY PART NUMBER") "311-9.31KCRCT-ND")
      )
      (libsource (lib "pqm_v2_lib_res") (part "RES_RC0805FR-079K31L_YAGEO"))
    )
    (comp (ref "R107")
      (value "10k")
      (footprint "RESC2013X065BN")
      (description "RES SMD 10K OHM 1% 1/8W 0805")
      (fields
        (field (name "TOLERANCE") "1%")
        (field (name "MANUFACTURER") "Yageo")
        (field (name "DIGIKEY PART NUMBER") "311-10.0KCRCT-ND")
      )
      (libsource (lib "pqm_v2_lib_res") (part "RES_RC0805FR-0710KL_YAGEO"))
    )
    (comp (ref "R108")
      (value "10k")
      (footprint "RESC2013X065BN")
      (description "RES SMD 10K OHM 1% 1/8W 0805")
      (fields
        (field (name "TOLERANCE") "1%")
        (field (name "MANUFACTURER") "Yageo")
        (field (name "DIGIKEY PART NUMBER") "311-10.0KCRCT-ND")
      )
      (libsource (lib "pqm_v2_lib_res") (part "RES_RC0805FR-0710KL_YAGEO"))
    )
    (comp (ref "R110")
      (value "1")
      (footprint "RESC2013X065BN")
      (description "RES SMD 1 OHM 1% 1/8W 0805")
      (fields
        (field (name "MANUFACTURER") "Yageo")
        (field (name "DIGIKEY PART NUMBER") "311-1.00CRCT-ND")
        (field (name "TOLERANCE") "1%")
      )
      (libsource (lib "pqm_v2_lib_res") (part "RES_RC0805FR-071RL_YAGEO"))
    )
    (comp (ref "R111")
      (value "510k")
      (footprint "RESC2013X065BN")
      (description "RES SMD 510K OHM 1% 1/8W 0805")
      (fields
        (field (name "MANUFACTURER") "Yageo")
        (field (name "DIGIKEY PART NUMBER") "311-510KCRCT-ND")
        (field (name "TOLERANCE") "1%")
      )
      (libsource (lib "pqm_v2_lib_res") (part "RES_RC0805FR-07510KL_YAGEO"))
    )
    (comp (ref "R113")
      (value "510k")
      (footprint "RESC2013X065BN")
      (description "RES SMD 510K OHM 1% 1/8W 0805")
      (fields
        (field (name "MANUFACTURER") "Yageo")
        (field (name "DIGIKEY PART NUMBER") "311-510KCRCT-ND")
        (field (name "TOLERANCE") "1%")
      )
      (libsource (lib "pqm_v2_lib_res") (part "RES_RC0805FR-07510KL_YAGEO"))
    )
    (comp (ref "R115")
      (value "510k")
      (footprint "RESC2013X065BN")
      (description "RES SMD 510K OHM 1% 1/8W 0805")
      (fields
        (field (name "MANUFACTURER") "Yageo")
        (field (name "DIGIKEY PART NUMBER") "311-510KCRCT-ND")
        (field (name "TOLERANCE") "1%")
      )
      (libsource (lib "pqm_v2_lib_res") (part "RES_RC0805FR-07510KL_YAGEO"))
    )
    (comp (ref "R117")
      (value "510k")
      (footprint "RESC2013X065BN")
      (description "RES SMD 510K OHM 1% 1/8W 0805")
      (fields
        (field (name "MANUFACTURER") "Yageo")
        (field (name "DIGIKEY PART NUMBER") "311-510KCRCT-ND")
        (field (name "TOLERANCE") "1%")
      )
      (libsource (lib "pqm_v2_lib_res") (part "RES_RC0805FR-07510KL_YAGEO"))
    )
    (comp (ref "R119")
      (value "510k")
      (footprint "RESC2013X065BN")
      (description "RES SMD 510K OHM 1% 1/8W 0805")
      (fields
        (field (name "MANUFACTURER") "Yageo")
        (field (name "DIGIKEY PART NUMBER") "311-510KCRCT-ND")
        (field (name "TOLERANCE") "1%")
      )
      (libsource (lib "pqm_v2_lib_res") (part "RES_RC0805FR-07510KL_YAGEO"))
    )
    (comp (ref "R121")
      (value "510k")
      (footprint "RESC2013X065BN")
      (description "RES SMD 510K OHM 1% 1/8W 0805")
      (fields
        (field (name "MANUFACTURER") "Yageo")
        (field (name "DIGIKEY PART NUMBER") "311-510KCRCT-ND")
        (field (name "TOLERANCE") "1%")
      )
      (libsource (lib "pqm_v2_lib_res") (part "RES_RC0805FR-07510KL_YAGEO"))
    )
    (comp (ref "U5")
      (value "TLV2474")
      (footprint "SOIC127P600-14AN")
      (description "IC OPAMP GP 2.8MHZ RRO 14SOIC")
      (fields
        (field (name "MANUFACTURER") "Texas Instrument")
        (field (name "DIGIKEY PART NUMBER") "296-2442-1-ND")
      )
      (libsource (lib "pqm_v2_lib_ic") (part "IC_TLV2474_ANALOG"))
    )
    (comp (ref "U6")
      (value "TLV2474")
      (footprint "SOIC127P600-14AN")
      (description "IC OPAMP GP 2.8MHZ RRO 14SOIC")
      (fields
        (field (name "MANUFACTURER") "Texas Instrument")
        (field (name "DIGIKEY PART NUMBER") "296-2442-1-ND")
      )
      (libsource (lib "pqm_v2_lib_ic") (part "IC_TLV2474_ANALOG"))
    )
    (comp (ref "U7")
      (value "IC_INA121U")
      (footprint "SOIC127P600-8BN")
      (description "IC OPAMP INSTR 600KHZ 8SOIC")
      (fields
        (field (name "DIGIKEY PART NUMBER") "INA121UA-ND")
        (field (name "MANUFACTURER PART NUMBER") "INA121UA")
      )
      (libsource (lib "pqm_v2_lib_ic") (part "IC_INA121U"))
    )
    (comp (ref "U8")
      (value "IC_INA121U")
      (footprint "SOIC127P600-8BN")
      (description "IC OPAMP INSTR 600KHZ 8SOIC")
      (fields
        (field (name "DIGIKEY PART NUMBER") "INA121UA-ND")
        (field (name "MANUFACTURER PART NUMBER") "INA121UA")
      )
      (libsource (lib "pqm_v2_lib_ic") (part "IC_INA121U"))
    )
    (comp (ref "U9")
      (value "IC_INA121U")
      (footprint "SOIC127P600-8BN")
      (description "IC OPAMP INSTR 600KHZ 8SOIC")
      (fields
        (field (name "DIGIKEY PART NUMBER") "INA121UA-ND")
        (field (name "MANUFACTURER PART NUMBER") "INA121UA")
      )
      (libsource (lib "pqm_v2_lib_ic") (part "IC_INA121U"))
    )
    (comp (ref "U10")
      (value "IC_INA121U")
      (footprint "SOIC127P600-8BN")
      (description "IC OPAMP INSTR 600KHZ 8SOIC")
      (fields
        (field (name "DIGIKEY PART NUMBER") "INA121UA-ND")
        (field (name "MANUFACTURER PART NUMBER") "INA121UA")
      )
      (libsource (lib "pqm_v2_lib_ic") (part "IC_INA121U"))
    )
    (comp (ref "U13")
      (value "ISL21010_1V5")
      (footprint "SOT23-3M")
      (description "IC VREF SERIES 1.5V SOT23-3")
      (fields
        (field (name "DIGIKEY PART NUMBER") "ISL21010CFH315Z-TKCT-ND")
        (field (name "MOUSER PART NUMBER") "968-ISL21010CFH315ZT")
      )
      (libsource (lib "pqm_v2_lib_ic") (part "IC_ISL21010_1V5_INTERSIL"))
    )
    (comp (ref "U14")
      (value "ISL21010_2V5")
      (footprint "SOT23-3M")
      (description "IC VREF SERIES 2.5V SOT23-3")
      (fields
        (field (name "DIGIKEY PART NUMBER") "ISL21010CFH325Z-TKCT-ND")
        (field (name "MANUFACTURER PART NUMBER") "ISL21010CFH325Z-TK")
      )
      (libsource (lib "pqm_v2_lib_ic") (part "IC_ISL21010_2V5_INTERSIL"))
    )
    (comp (ref "U19")
      (value "ISL21010_1V5")
      (footprint "SOT23-3M")
      (description "IC VREF SERIES 1.5V SOT23-3")
      (fields
        (field (name "DIGIKEY PART NUMBER") "ISL21010CFH315Z-TKCT-ND")
        (field (name "MOUSER PART NUMBER") "968-ISL21010CFH315ZT")
      )
      (libsource (lib "pqm_v2_lib_ic") (part "IC_ISL21010_1V5_INTERSIL"))
    )
  )
  (nets
    (net (code "1") (name "+5v") (class "Default")
      (node (ref "C35") (pin "1") (pinfunction "T1_1") (pintype "passive"))
      (node (ref "C44") (pin "1") (pinfunction "T1_1") (pintype "passive"))
      (node (ref "C69") (pin "1") (pinfunction "T1_1") (pintype "passive"))
      (node (ref "C70") (pin "1") (pinfunction "T1_1") (pintype "passive"))
      (node (ref "C71") (pin "1") (pinfunction "T1_1") (pintype "passive"))
      (node (ref "C72") (pin "1") (pinfunction "T1_1") (pintype "passive"))
      (node (ref "C75") (pin "1") (pinfunction "T1_1") (pintype "passive"))
      (node (ref "C76") (pin "1") (pinfunction "T1_1") (pintype "passive"))
      (node (ref "C93") (pin "1") (pinfunction "T1_1") (pintype "passive"))
      (node (ref "U10") (pin "7") (pinfunction "+V_7") (pintype "power_in"))
      (node (ref "U13") (pin "1") (pinfunction "VIN_1") (pintype "passive"))
      (node (ref "U14") (pin "1") (pinfunction "VIN_1") (pintype "passive"))
      (node (ref "U19") (pin "1") (pinfunction "VIN_1") (pintype "passive"))
      (node (ref "U5") (pin "4") (pinfunction "VDD_4") (pintype "passive"))
      (node (ref "U6") (pin "4") (pinfunction "VDD_4") (pintype "passive"))
      (node (ref "U7") (pin "7") (pinfunction "+V_7") (pintype "power_in"))
      (node (ref "U8") (pin "7") (pinfunction "+V_7") (pintype "power_in"))
      (node (ref "U9") (pin "7") (pinfunction "+V_7") (pintype "power_in"))
    )
    (net (code "2") (name "/IL_1V5_A") (class "Default")
      (node (ref "C24") (pin "1") (pinfunction "T1_1") (pintype "passive"))
      (node (ref "C38") (pin "1") (pinfunction "T1_1") (pintype "passive"))
      (node (ref "C78") (pin "1") (pinfunction "T1_1") (pintype "passive"))
      (node (ref "R66") (pin "2") (pinfunction "T2_2") (pintype "passive"))
      (node (ref "R79") (pin "2") (pinfunction "T2_2") (pintype "passive"))
      (node (ref "U13") (pin "2") (pinfunction "VOUT_2") (pintype "passive"))
    )
    (net (code "3") (name "/IL_1V5_B") (class "Default")
      (node (ref "C42") (pin "1") (pinfunction "T1_1") (pintype "passive"))
      (node (ref "C47") (pin "1") (pinfunction "T1_1") (pintype "passive"))
      (node (ref "C94") (pin "1") (pinfunction "T1_1") (pintype "passive"))
      (node (ref "R105") (pin "2") (pinfunction "T2_2") (pintype "passive"))
      (node (ref "R92") (pin "2") (pinfunction "T2_2") (pintype "passive"))
      (node (ref "U19") (pin "2") (pinfunction "VOUT_2") (pintype "passive"))
    )
    (net (code "4") (name "/IL_2V5_A") (class "Default")
      (node (ref "C77") (pin "1") (pinfunction "T1_1") (pintype "passive"))
      (node (ref "C79") (pin "2") (pinfunction "T2_2") (pintype "passive"))
      (node (ref "C80") (pin "1") (pinfunction "T1_1") (pintype "passive"))
      (node (ref "C81") (pin "2") (pinfunction "T2_2") (pintype "passive"))
      (node (ref "C82") (pin "1") (pinfunction "T1_1") (pintype "passive"))
      (node (ref "C83") (pin "2") (pinfunction "T2_2") (pintype "passive"))
      (node (ref "C84") (pin "1") (pinfunction "T1_1") (pintype "passive"))
      (node (ref "C85") (pin "2") (pinfunction "T2_2") (pintype "passive"))
      (node (ref "C86") (pin "1") (pinfunction "T1_1") (pintype "passive"))
      (node (ref "R103") (pin "2") (pinfunction "T2_2") (pintype "passive"))
      (node (ref "R111") (pin "1") (pinfunction "T1_1") (pintype "passive"))
      (node (ref "R113") (pin "2") (pinfunction "T2_2") (pintype "passive"))
      (node (ref "R115") (pin "1") (pinfunction "T1_1") (pintype "passive"))
      (node (ref "R117") (pin "2") (pinfunction "T2_2") (pintype "passive"))
      (node (ref "R119") (pin "1") (pinfunction "T1_1") (pintype "passive"))
      (node (ref "R121") (pin "2") (pinfunction "T2_2") (pintype "passive"))
      (node (ref "R14") (pin "1") (pinfunction "T1_1") (pintype "passive"))
      (node (ref "U10") (pin "5") (pinfunction "REF_5") (pintype "passive"))
      (node (ref "U14") (pin "2") (pinfunction "VOUT_2") (pintype "passive"))
      (node (ref "U7") (pin "5") (pinfunction "REF_5") (pintype "passive"))
      (node (ref "U8") (pin "5") (pinfunction "REF_5") (pintype "passive"))
      (node (ref "U9") (pin "5") (pinfunction "REF_5") (pintype "passive"))
    )
    (net (code "5") (name "AGND") (class "Default")
      (node (ref "C31") (pin "1") (pinfunction "T1_1") (pintype "passive"))
      (node (ref "C35") (pin "2") (pinfunction "T2_2") (pintype "passive"))
      (node (ref "C39") (pin "1") (pinfunction "T1_1") (pintype "passive"))
      (node (ref "C43") (pin "1") (pinfunction "T1_1") (pintype "passive"))
      (node (ref "C44") (pin "2") (pinfunction "T2_2") (pintype "passive"))
      (node (ref "C48") (pin "1") (pinfunction "T1_1") (pintype "passive"))
      (node (ref "C69") (pin "2") (pinfunction "T2_2") (pintype "passive"))
      (node (ref "C70") (pin "2") (pinfunction "T2_2") (pintype "passive"))
      (node (ref "C71") (pin "2") (pinfunction "T2_2") (pintype "passive"))
      (node (ref "C72") (pin "2") (pinfunction "T2_2") (pintype "passive"))
      (node (ref "C75") (pin "2") (pinfunction "T2_2") (pintype "passive"))
      (node (ref "C76") (pin "2") (pinfunction "T2_2") (pintype "passive"))
      (node (ref "C77") (pin "2") (pinfunction "T2_2") (pintype "passive"))
      (node (ref "C78") (pin "2") (pinfunction "T2_2") (pintype "passive"))
      (node (ref "C93") (pin "2") (pinfunction "T2_2") (pintype "passive"))
      (node (ref "C94") (pin "2") (pinfunction "T2_2") (pintype "passive"))
      (node (ref "R106") (pin "1") (pinfunction "T1_1") (pintype "passive"))
      (node (ref "R107") (pin "2") (pinfunction "T2_2") (pintype "passive"))
      (node (ref "R67") (pin "1") (pinfunction "T1_1") (pintype "passive"))
      (node (ref "R68") (pin "2") (pinfunction "T2_2") (pintype "passive"))
      (node (ref "R80") (pin "1") (pinfunction "T1_1") (pintype "passive"))
      (node (ref "R81") (pin "2") (pinfunction "T2_2") (pintype "passive"))
      (node (ref "R93") (pin "1") (pinfunction "T1_1") (pintype "passive"))
      (node (ref "R94") (pin "2") (pinfunction "T2_2") (pintype "passive"))
      (node (ref "U10") (pin "4") (pinfunction "-V_4") (pintype "power_in"))
      (node (ref "U13") (pin "3") (pinfunction "GND_3") (pintype "passive"))
      (node (ref "U14") (pin "3") (pinfunction "GND_3") (pintype "passive"))
      (node (ref "U19") (pin "3") (pinfunction "GND_3") (pintype "passive"))
      (node (ref "U5") (pin "11") (pinfunction "GND_11") (pintype "passive"))
      (node (ref "U6") (pin "11") (pinfunction "GND_11") (pintype "passive"))
      (node (ref "U7") (pin "4") (pinfunction "-V_4") (pintype "power_in"))
      (node (ref "U8") (pin "4") (pinfunction "-V_4") (pintype "power_in"))
      (node (ref "U9") (pin "4") (pinfunction "-V_4") (pintype "power_in"))
    )
    (net (code "6") (name "IL1") (class "Default")
      (node (ref "C19") (pin "2") (pinfunction "T2_2") (pintype "passive"))
      (node (ref "R69") (pin "1") (pinfunction "T1_1") (pintype "passive"))
      (node (ref "U5") (pin "14") (pinfunction "OUTD_14") (pintype "passive"))
    )
    (net (code "7") (name "IL2") (class "Default")
      (node (ref "C37") (pin "2") (pinfunction "T2_2") (pintype "passive"))
      (node (ref "R82") (pin "1") (pinfunction "T1_1") (pintype "passive"))
      (node (ref "U5") (pin "8") (pinfunction "OUTC_8") (pintype "passive"))
    )
    (net (code "8") (name "IL3") (class "Default")
      (node (ref "C41") (pin "2") (pinfunction "T2_2") (pintype "passive"))
      (node (ref "R95") (pin "1") (pinfunction "T1_1") (pintype "passive"))
      (node (ref "U6") (pin "14") (pinfunction "OUTD_14") (pintype "passive"))
    )
    (net (code "9") (name "IL4") (class "Default")
      (node (ref "C46") (pin "2") (pinfunction "T2_2") (pintype "passive"))
      (node (ref "R108") (pin "1") (pinfunction "T1_1") (pintype "passive"))
      (node (ref "U6") (pin "8") (pinfunction "OUTC_8") (pintype "passive"))
    )
    (net (code "10") (name "Net-(C12-T1)") (class "Default")
      (node (ref "C12") (pin "1") (pinfunction "T1_1") (pintype "passive"))
      (node (ref "R32") (pin "1") (pinfunction "T1_1") (pintype "passive"))
      (node (ref "R46") (pin "2") (pinfunction "T2_2") (pintype "passive"))
      (node (ref "U5") (pin "2") (pinfunction "INA-_2") (pintype "passive"))
    )
    (net (code "11") (name "Net-(C12-T2)") (class "Default")
      (node (ref "C12") (pin "2") (pinfunction "T2_2") (pintype "passive"))
      (node (ref "R46") (pin "1") (pinfunction "T1_1") (pintype "passive"))
      (node (ref "R61") (pin "2") (pinfunction "T2_2") (pintype "passive"))
      (node (ref "U5") (pin "1") (pinfunction "OUTA_1") (pintype "passive"))
    )
    (net (code "12") (name "Net-(C19-T1)") (class "Default")
      (node (ref "C19") (pin "1") (pinfunction "T1_1") (pintype "passive"))
      (node (ref "R61") (pin "1") (pinfunction "T1_1") (pintype "passive"))
      (node (ref "R62") (pin "2") (pinfunction "T2_2") (pintype "passive"))
      (node (ref "R67") (pin "2") (pinfunction "T2_2") (pintype "passive"))
    )
    (net (code "13") (name "Net-(C24-T2)") (class "Default")
      (node (ref "C24") (pin "2") (pinfunction "T2_2") (pintype "passive"))
      (node (ref "R65") (pin "1") (pinfunction "T1_1") (pintype "passive"))
      (node (ref "R66") (pin "1") (pinfunction "T1_1") (pintype "passive"))
      (node (ref "U5") (pin "3") (pinfunction "INA+_3") (pintype "passive"))
    )
    (net (code "14") (name "Net-(C31-T2)") (class "Default")
      (node (ref "C31") (pin "2") (pinfunction "T2_2") (pintype "passive"))
      (node (ref "R62") (pin "1") (pinfunction "T1_1") (pintype "passive"))
      (node (ref "U5") (pin "13") (pinfunction "IND-_13") (pintype "passive"))
    )
    (net (code "15") (name "Net-(C36-T1)") (class "Default")
      (node (ref "C36") (pin "1") (pinfunction "T1_1") (pintype "passive"))
      (node (ref "R72") (pin "1") (pinfunction "T1_1") (pintype "passive"))
      (node (ref "R73") (pin "2") (pinfunction "T2_2") (pintype "passive"))
      (node (ref "U5") (pin "6") (pinfunction "INB-_6") (pintype "passive"))
    )
    (net (code "16") (name "Net-(C36-T2)") (class "Default")
      (node (ref "C36") (pin "2") (pinfunction "T2_2") (pintype "passive"))
      (node (ref "R73") (pin "1") (pinfunction "T1_1") (pintype "passive"))
      (node (ref "R74") (pin "2") (pinfunction "T2_2") (pintype "passive"))
      (node (ref "U5") (pin "7") (pinfunction "OUTB_7") (pintype "passive"))
    )
    (net (code "17") (name "Net-(C37-T1)") (class "Default")
      (node (ref "C37") (pin "1") (pinfunction "T1_1") (pintype "passive"))
      (node (ref "R74") (pin "1") (pinfunction "T1_1") (pintype "passive"))
      (node (ref "R75") (pin "2") (pinfunction "T2_2") (pintype "passive"))
      (node (ref "R80") (pin "2") (pinfunction "T2_2") (pintype "passive"))
    )
    (net (code "18") (name "Net-(C38-T2)") (class "Default")
      (node (ref "C38") (pin "2") (pinfunction "T2_2") (pintype "passive"))
      (node (ref "R78") (pin "1") (pinfunction "T1_1") (pintype "passive"))
      (node (ref "R79") (pin "1") (pinfunction "T1_1") (pintype "passive"))
      (node (ref "U5") (pin "5") (pinfunction "INB+_5") (pintype "passive"))
    )
    (net (code "19") (name "Net-(C39-T2)") (class "Default")
      (node (ref "C39") (pin "2") (pinfunction "T2_2") (pintype "passive"))
      (node (ref "R75") (pin "1") (pinfunction "T1_1") (pintype "passive"))
      (node (ref "U5") (pin "9") (pinfunction "INC-_9") (pintype "passive"))
    )
    (net (code "20") (name "Net-(C40-T1)") (class "Default")
      (node (ref "C40") (pin "1") (pinfunction "T1_1") (pintype "passive"))
      (node (ref "R85") (pin "1") (pinfunction "T1_1") (pintype "passive"))
      (node (ref "R86") (pin "2") (pinfunction "T2_2") (pintype "passive"))
      (node (ref "U6") (pin "2") (pinfunction "INA-_2") (pintype "passive"))
    )
    (net (code "21") (name "Net-(C40-T2)") (class "Default")
      (node (ref "C40") (pin "2") (pinfunction "T2_2") (pintype "passive"))
      (node (ref "R86") (pin "1") (pinfunction "T1_1") (pintype "passive"))
      (node (ref "R87") (pin "2") (pinfunction "T2_2") (pintype "passive"))
      (node (ref "U6") (pin "1") (pinfunction "OUTA_1") (pintype "passive"))
    )
    (net (code "22") (name "Net-(C41-T1)") (class "Default")
      (node (ref "C41") (pin "1") (pinfunction "T1_1") (pintype "passive"))
      (node (ref "R87") (pin "1") (pinfunction "T1_1") (pintype "passive"))
      (node (ref "R88") (pin "2") (pinfunction "T2_2") (pintype "passive"))
      (node (ref "R93") (pin "2") (pinfunction "T2_2") (pintype "passive"))
    )
    (net (code "23") (name "Net-(C42-T2)") (class "Default")
      (node (ref "C42") (pin "2") (pinfunction "T2_2") (pintype "passive"))
      (node (ref "R91") (pin "1") (pinfunction "T1_1") (pintype "passive"))
      (node (ref "R92") (pin "1") (pinfunction "T1_1") (pintype "passive"))
      (node (ref "U6") (pin "3") (pinfunction "INA+_3") (pintype "passive"))
    )
    (net (code "24") (name "Net-(C43-T2)") (class "Default")
      (node (ref "C43") (pin "2") (pinfunction "T2_2") (pintype "passive"))
      (node (ref "R88") (pin "1") (pinfunction "T1_1") (pintype "passive"))
      (node (ref "U6") (pin "13") (pinfunction "IND-_13") (pintype "passive"))
    )
    (net (code "25") (name "Net-(C45-T1)") (class "Default")
      (node (ref "C45") (pin "1") (pinfunction "T1_1") (pintype "passive"))
      (node (ref "R98") (pin "1") (pinfunction "T1_1") (pintype "passive"))
      (node (ref "R99") (pin "2") (pinfunction "T2_2") (pintype "passive"))
      (node (ref "U6") (pin "6") (pinfunction "INB-_6") (pintype "passive"))
    )
    (net (code "26") (name "Net-(C45-T2)") (class "Default")
      (node (ref "C45") (pin "2") (pinfunction "T2_2") (pintype "passive"))
      (node (ref "R100") (pin "2") (pinfunction "T2_2") (pintype "passive"))
      (node (ref "R99") (pin "1") (pinfunction "T1_1") (pintype "passive"))
      (node (ref "U6") (pin "7") (pinfunction "OUTB_7") (pintype "passive"))
    )
    (net (code "27") (name "Net-(C46-T1)") (class "Default")
      (node (ref "C46") (pin "1") (pinfunction "T1_1") (pintype "passive"))
      (node (ref "R100") (pin "1") (pinfunction "T1_1") (pintype "passive"))
      (node (ref "R101") (pin "2") (pinfunction "T2_2") (pintype "passive"))
      (node (ref "R106") (pin "2") (pinfunction "T2_2") (pintype "passive"))
    )
    (net (code "28") (name "Net-(C47-T2)") (class "Default")
      (node (ref "C47") (pin "2") (pinfunction "T2_2") (pintype "passive"))
      (node (ref "R104") (pin "1") (pinfunction "T1_1") (pintype "passive"))
      (node (ref "R105") (pin "1") (pinfunction "T1_1") (pintype "passive"))
      (node (ref "U6") (pin "5") (pinfunction "INB+_5") (pintype "passive"))
    )
    (net (code "29") (name "Net-(C48-T2)") (class "Default")
      (node (ref "C48") (pin "2") (pinfunction "T2_2") (pintype "passive"))
      (node (ref "R101") (pin "1") (pinfunction "T1_1") (pintype "passive"))
      (node (ref "U6") (pin "9") (pinfunction "INC-_9") (pintype "passive"))
    )
    (net (code "30") (name "Net-(C79-T1)") (class "Default")
      (node (ref "C79") (pin "1") (pinfunction "T1_1") (pintype "passive"))
      (node (ref "J13") (pin "1") (pinfunction "1_1") (pintype "output"))
      (node (ref "R110") (pin "2") (pinfunction "T2_2") (pintype "passive"))
      (node (ref "R14") (pin "2") (pinfunction "T2_2") (pintype "passive"))
      (node (ref "U7") (pin "2") (pinfunction "IN-_2") (pintype "input"))
    )
    (net (code "31") (name "Net-(C80-T2)") (class "Default")
      (node (ref "C80") (pin "2") (pinfunction "T2_2") (pintype "passive"))
      (node (ref "J13") (pin "2") (pinfunction "2_2") (pintype "output"))
      (node (ref "R103") (pin "1") (pinfunction "T1_1") (pintype "passive"))
      (node (ref "R110") (pin "1") (pinfunction "T1_1") (pintype "passive"))
      (node (ref "U7") (pin "3") (pinfunction "IN+_3") (pintype "input"))
    )
    (net (code "32") (name "Net-(C81-T1)") (class "Default")
      (node (ref "C81") (pin "1") (pinfunction "T1_1") (pintype "passive"))
      (node (ref "J13") (pin "3") (pinfunction "3_3") (pintype "output"))
      (node (ref "R111") (pin "2") (pinfunction "T2_2") (pintype "passive"))
      (node (ref "R63") (pin "2") (pinfunction "T2_2") (pintype "passive"))
      (node (ref "U8") (pin "2") (pinfunction "IN-_2") (pintype "input"))
    )
    (net (code "33") (name "Net-(C82-T2)") (class "Default")
      (node (ref "C82") (pin "2") (pinfunction "T2_2") (pintype "passive"))
      (node (ref "J13") (pin "4") (pinfunction "4_4") (pintype "output"))
      (node (ref "R113") (pin "1") (pinfunction "T1_1") (pintype "passive"))
      (node (ref "R63") (pin "1") (pinfunction "T1_1") (pintype "passive"))
      (node (ref "U8") (pin "3") (pinfunction "IN+_3") (pintype "input"))
    )
    (net (code "34") (name "Net-(C83-T1)") (class "Default")
      (node (ref "C83") (pin "1") (pinfunction "T1_1") (pintype "passive"))
      (node (ref "J13") (pin "5") (pinfunction "5_5") (pintype "output"))
      (node (ref "R115") (pin "2") (pinfunction "T2_2") (pintype "passive"))
      (node (ref "R70") (pin "2") (pinfunction "T2_2") (pintype "passive"))
      (node (ref "U9") (pin "2") (pinfunction "IN-_2") (pintype "input"))
    )
    (net (code "35") (name "Net-(C84-T2)") (class "Default")
      (node (ref "C84") (pin "2") (pinfunction "T2_2") (pintype "passive"))
      (node (ref "J13") (pin "6") (pinfunction "6_6") (pintype "output"))
      (node (ref "R117") (pin "1") (pinfunction "T1_1") (pintype "passive"))
      (node (ref "R70") (pin "1") (pinfunction "T1_1") (pintype "passive"))
      (node (ref "U9") (pin "3") (pinfunction "IN+_3") (pintype "input"))
    )
    (net (code "36") (name "Net-(C85-T1)") (class "Default")
      (node (ref "C85") (pin "1") (pinfunction "T1_1") (pintype "passive"))
      (node (ref "J13") (pin "7") (pinfunction "7_7") (pintype "output"))
      (node (ref "R119") (pin "2") (pinfunction "T2_2") (pintype "passive"))
      (node (ref "R76") (pin "2") (pinfunction "T2_2") (pintype "passive"))
      (node (ref "U10") (pin "2") (pinfunction "IN-_2") (pintype "input"))
    )
    (net (code "37") (name "Net-(C86-T2)") (class "Default")
      (node (ref "C86") (pin "2") (pinfunction "T2_2") (pintype "passive"))
      (node (ref "J13") (pin "8") (pinfunction "8_8") (pintype "output"))
      (node (ref "R121") (pin "1") (pinfunction "T1_1") (pintype "passive"))
      (node (ref "R76") (pin "1") (pinfunction "T1_1") (pintype "passive"))
      (node (ref "U10") (pin "3") (pinfunction "IN+_3") (pintype "input"))
    )
    (net (code "38") (name "Net-(R18-T1)") (class "Default")
      (node (ref "R18") (pin "1") (pinfunction "T1_1") (pintype "passive"))
      (node (ref "U7") (pin "8") (pinfunction "RG_8") (pintype "passive"))
    )
    (net (code "39") (name "Net-(R18-T2)") (class "Default")
      (node (ref "R18") (pin "2") (pinfunction "T2_2") (pintype "passive"))
      (node (ref "U7") (pin "1") (pinfunction "RG_1") (pintype "passive"))
    )
    (net (code "40") (name "Net-(R64-T1)") (class "Default")
      (node (ref "R64") (pin "1") (pinfunction "T1_1") (pintype "passive"))
      (node (ref "U8") (pin "8") (pinfunction "RG_8") (pintype "passive"))
    )
    (net (code "41") (name "Net-(R64-T2)") (class "Default")
      (node (ref "R64") (pin "2") (pinfunction "T2_2") (pintype "passive"))
      (node (ref "U8") (pin "1") (pinfunction "RG_1") (pintype "passive"))
    )
    (net (code "42") (name "Net-(R65-T2)") (class "Default")
      (node (ref "R65") (pin "2") (pinfunction "T2_2") (pintype "passive"))
      (node (ref "U7") (pin "6") (pinfunction "OUT_6") (pintype "output"))
    )
    (net (code "43") (name "Net-(R68-T1)") (class "Default")
      (node (ref "R68") (pin "1") (pinfunction "T1_1") (pintype "passive"))
      (node (ref "R69") (pin "2") (pinfunction "T2_2") (pintype "passive"))
      (node (ref "U5") (pin "12") (pinfunction "IND+_12") (pintype "passive"))
    )
    (net (code "44") (name "Net-(R71-T1)") (class "Default")
      (node (ref "R71") (pin "1") (pinfunction "T1_1") (pintype "passive"))
      (node (ref "U9") (pin "8") (pinfunction "RG_8") (pintype "passive"))
    )
    (net (code "45") (name "Net-(R71-T2)") (class "Default")
      (node (ref "R71") (pin "2") (pinfunction "T2_2") (pintype "passive"))
      (node (ref "U9") (pin "1") (pinfunction "RG_1") (pintype "passive"))
    )
    (net (code "46") (name "Net-(R77-T1)") (class "Default")
      (node (ref "R77") (pin "1") (pinfunction "T1_1") (pintype "passive"))
      (node (ref "U10") (pin "8") (pinfunction "RG_8") (pintype "passive"))
    )
    (net (code "47") (name "Net-(R77-T2)") (class "Default")
      (node (ref "R77") (pin "2") (pinfunction "T2_2") (pintype "passive"))
      (node (ref "U10") (pin "1") (pinfunction "RG_1") (pintype "passive"))
    )
    (net (code "48") (name "Net-(R78-T2)") (class "Default")
      (node (ref "R78") (pin "2") (pinfunction "T2_2") (pintype "passive"))
      (node (ref "U8") (pin "6") (pinfunction "OUT_6") (pintype "output"))
    )
    (net (code "49") (name "Net-(R81-T1)") (class "Default")
      (node (ref "R81") (pin "1") (pinfunction "T1_1") (pintype "passive"))
      (node (ref "R82") (pin "2") (pinfunction "T2_2") (pintype "passive"))
      (node (ref "U5") (pin "10") (pinfunction "INC+_10") (pintype "passive"))
    )
    (net (code "50") (name "Net-(R91-T2)") (class "Default")
      (node (ref "R91") (pin "2") (pinfunction "T2_2") (pintype "passive"))
      (node (ref "U9") (pin "6") (pinfunction "OUT_6") (pintype "output"))
    )
    (net (code "51") (name "Net-(R94-T1)") (class "Default")
      (node (ref "R94") (pin "1") (pinfunction "T1_1") (pintype "passive"))
      (node (ref "R95") (pin "2") (pinfunction "T2_2") (pintype "passive"))
      (node (ref "U6") (pin "12") (pinfunction "IND+_12") (pintype "passive"))
    )
    (net (code "52") (name "Net-(R104-T2)") (class "Default")
      (node (ref "R104") (pin "2") (pinfunction "T2_2") (pintype "passive"))
      (node (ref "U10") (pin "6") (pinfunction "OUT_6") (pintype "output"))
    )
    (net (code "53") (name "Net-(R107-T1)") (class "Default")
      (node (ref "R107") (pin "1") (pinfunction "T1_1") (pintype "passive"))
      (node (ref "R108") (pin "2") (pinfunction "T2_2") (pintype "passive"))
      (node (ref "U6") (pin "10") (pinfunction "INC+_10") (pintype "passive"))
    )
    (net (code "54") (name "unconnected-(R32-T2-Pad2)") (class "Default")
      (node (ref "R32") (pin "2") (pinfunction "T2_2") (pintype "passive+no_connect"))
    )
    (net (code "55") (name "unconnected-(R72-T2-Pad2)") (class "Default")
      (node (ref "R72") (pin "2") (pinfunction "T2_2") (pintype "passive+no_connect"))
    )
    (net (code "56") (name "unconnected-(R85-T2-Pad2)") (class "Default")
      (node (ref "R85") (pin "2") (pinfunction "T2_2") (pintype "passive+no_connect"))
    )
    (net (code "57") (name "unconnected-(R98-T2-Pad2)") (class "Default")
      (node (ref "R98") (pin "2") (pinfunction "T2_2") (pintype "passive+no_connect"))
    )
  )
)
